# Main.net
KiCad netlist of a schematic drawn in EAGLE
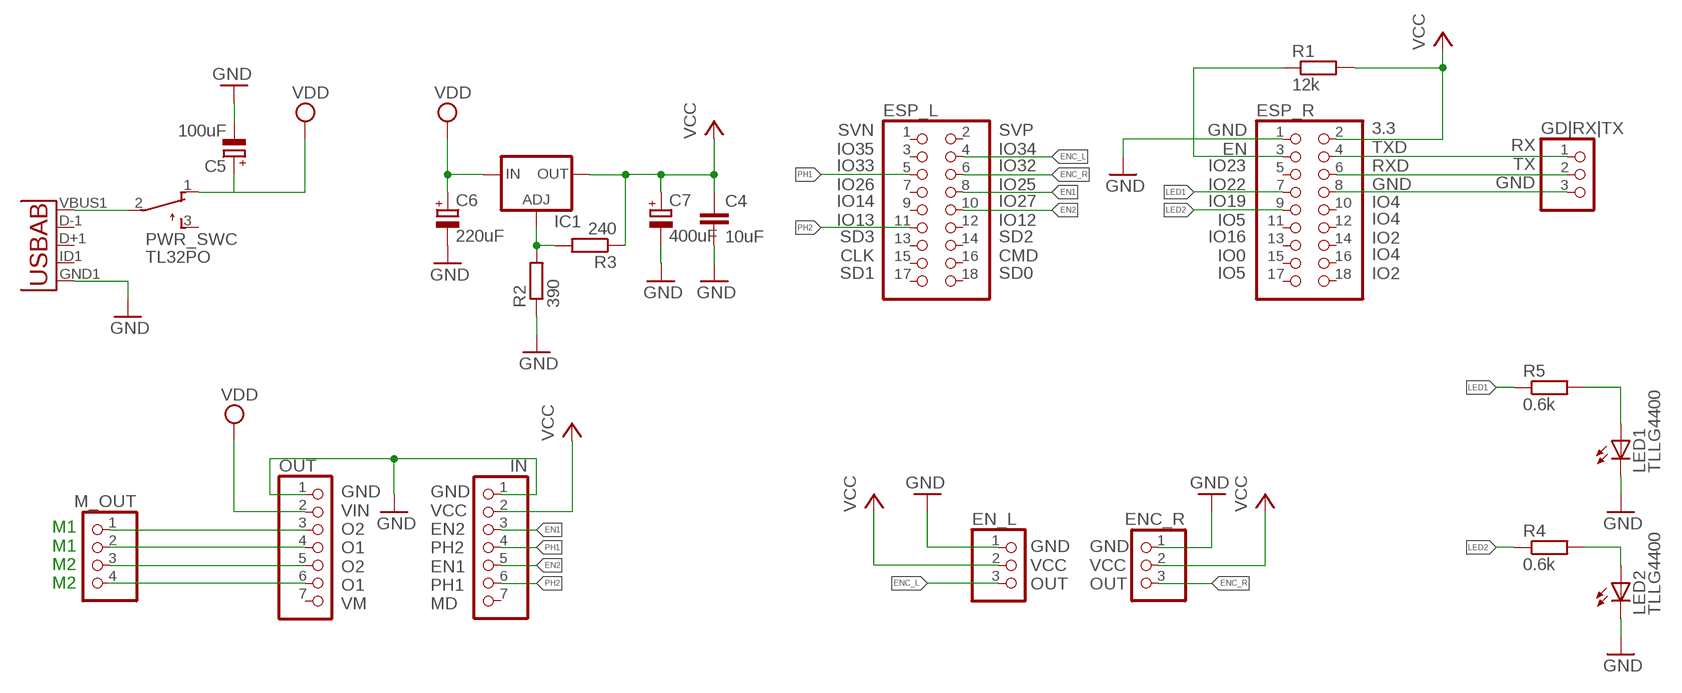
[diagram p0: schematic, sheet 1]

(export (version "E")
  (design (tool "Eeschema 10.0.6"))
  (components
    (comp (ref "C4")
      (value "10uF")
      (footprint "eagle-import:C050-025X075")
      (libsource (lib "eagle-import") (part "C-EU050-025X075"))
    )
    (comp (ref "C5")
      (value "100uF")
      (footprint "eagle-import:E2,5-6")
      (libsource (lib "eagle-import") (part "CPOL-EUE2.5-6"))
    )
    (comp (ref "C6")
      (value "220uF")
      (footprint "eagle-import:E2,5-6")
      (libsource (lib "eagle-import") (part "CPOL-EUE2.5-6"))
    )
    (comp (ref "C7")
      (value "400uF")
      (footprint "eagle-import:E2,5-6")
      (libsource (lib "eagle-import") (part "CPOL-EUE2.5-6"))
    )
    (comp (ref "ENC_R")
      (value "PINHD-1X3")
      (footprint "eagle-import:1X03")
      (libsource (lib "eagle-import") (part "PINHD-1X3"))
    )
    (comp (ref "EN_L")
      (value "PINHD-1X3")
      (footprint "eagle-import:1X03")
      (libsource (lib "eagle-import") (part "PINHD-1X3"))
    )
    (comp (ref "ESP_L")
      (value "PINHD-2X9")
      (footprint "eagle-import:2X09")
      (libsource (lib "eagle-import") (part "PINHD-2X9"))
    )
    (comp (ref "ESP_R")
      (value "PINHD-2X9")
      (footprint "eagle-import:2X09")
      (libsource (lib "eagle-import") (part "PINHD-2X9"))
    )
    (comp (ref "GD|RX|TX")
      (value "PINHD-1X3")
      (footprint "eagle-import:1X03")
      (libsource (lib "eagle-import") (part "PINHD-1X3"))
    )
    (comp (ref "IC1")
      (value "LM317TS")
      (footprint "eagle-import:317TS")
      (libsource (lib "eagle-import") (part "LM317TS"))
    )
    (comp (ref "IN")
      (value "PINHD-1X7")
      (footprint "eagle-import:1X07")
      (libsource (lib "eagle-import") (part "PINHD-1X7"))
    )
    (comp (ref "LED1")
      (value "TLLG4400")
      (footprint "eagle-import:LED3MM")
      (fields (field (name "MF") "VISHAY SEMICONDUCTOR"))
      (libsource (lib "eagle-import") (part "TLLG4400"))
    )
    (comp (ref "LED2")
      (value "TLLG4400")
      (footprint "eagle-import:LED3MM")
      (fields (field (name "MF") "VISHAY SEMICONDUCTOR"))
      (libsource (lib "eagle-import") (part "TLLG4400"))
    )
    (comp (ref "M_OUT")
      (value "PINHD-1X4")
      (footprint "eagle-import:1X04")
      (libsource (lib "eagle-import") (part "PINHD-1X4"))
    )
    (comp (ref "OUT")
      (value "PINHD-1X7")
      (footprint "eagle-import:1X07")
      (libsource (lib "eagle-import") (part "PINHD-1X7"))
    )
    (comp (ref "PWR_SWC")
      (value "TL32PO")
      (footprint "eagle-import:TL3XPO")
      (libsource (lib "eagle-import") (part "TL32PO"))
    )
    (comp (ref "R1")
      (value "12k")
      (footprint "eagle-import:0207_10")
      (libsource (lib "eagle-import") (part "R-EU_0207/10"))
    )
    (comp (ref "R2")
      (value "390")
      (footprint "eagle-import:0207_10")
      (libsource (lib "eagle-import") (part "R-EU_0207/10"))
    )
    (comp (ref "R3")
      (value "240")
      (footprint "eagle-import:0207_10")
      (libsource (lib "eagle-import") (part "R-EU_0207/10"))
    )
    (comp (ref "R4")
      (value "0.6k")
      (footprint "eagle-import:0207_10")
      (libsource (lib "eagle-import") (part "R-EU_0207/10"))
    )
    (comp (ref "R5")
      (value "0.6k")
      (footprint "eagle-import:0207_10")
      (libsource (lib "eagle-import") (part "R-EU_0207/10"))
    )
    (comp (ref "U3")
      (value "USB\"\"")
      (footprint "eagle-import:USB-MICRO-SMD")
      (libsource (lib "eagle-import") (part "USB{dblquote}{dblquote}"))
    )
  )
  (nets
    (net (code "1") (name "EN1") (class "Default")
      (node (ref "ESP_L") (pin "8") (pinfunction "8_8") (pintype "passive"))
      (node (ref "IN") (pin "3") (pinfunction "3_3") (pintype "passive"))
    )
    (net (code "2") (name "EN2") (class "Default")
      (node (ref "ESP_L") (pin "10") (pinfunction "10_10") (pintype "passive"))
      (node (ref "IN") (pin "5") (pinfunction "5_5") (pintype "passive"))
    )
    (net (code "3") (name "ENC_L") (class "Default")
      (node (ref "EN_L") (pin "3") (pinfunction "3_3") (pintype "passive"))
      (node (ref "ESP_L") (pin "4") (pinfunction "4_4") (pintype "passive"))
    )
    (net (code "4") (name "ENC_R") (class "Default")
      (node (ref "ENC_R") (pin "3") (pinfunction "3_3") (pintype "passive"))
      (node (ref "ESP_L") (pin "6") (pinfunction "6_6") (pintype "passive"))
    )
    (net (code "5") (name "GND") (class "Default")
      (node (ref "C4") (pin "2") (pinfunction "2_2") (pintype "passive"))
      (node (ref "C5") (pin "-") (pinfunction "-_-") (pintype "passive"))
      (node (ref "C6") (pin "-") (pinfunction "-_-") (pintype "passive"))
      (node (ref "C7") (pin "-") (pinfunction "-_-") (pintype "passive"))
      (node (ref "ENC_R") (pin "1") (pinfunction "1_1") (pintype "passive"))
      (node (ref "EN_L") (pin "1") (pinfunction "1_1") (pintype "passive"))
      (node (ref "ESP_R") (pin "1") (pinfunction "1_1") (pintype "passive"))
      (node (ref "IN") (pin "1") (pinfunction "1_1") (pintype "passive"))
      (node (ref "LED1") (pin "K") (pinfunction "C_K") (pintype "passive"))
      (node (ref "LED2") (pin "K") (pinfunction "C_K") (pintype "passive"))
      (node (ref "OUT") (pin "1") (pinfunction "1_1") (pintype "passive"))
      (node (ref "R2") (pin "1") (pinfunction "1_1") (pintype "passive"))
      (node (ref "U3") (pin "GND1") (pinfunction "GND_GND1") (pintype "bidirectional"))
    )
    (net (code "6") (name "LED1") (class "Default")
      (node (ref "ESP_R") (pin "7") (pinfunction "7_7") (pintype "passive"))
      (node (ref "R5") (pin "1") (pinfunction "1_1") (pintype "passive"))
    )
    (net (code "7") (name "LED2") (class "Default")
      (node (ref "ESP_R") (pin "9") (pinfunction "9_9") (pintype "passive"))
      (node (ref "R4") (pin "1") (pinfunction "1_1") (pintype "passive"))
    )
    (net (code "8") (name "Net-(ESP_R-Pad3)") (class "Default")
      (node (ref "ESP_R") (pin "3") (pinfunction "3_3") (pintype "passive"))
      (node (ref "R1") (pin "1") (pinfunction "1_1") (pintype "passive"))
    )
    (net (code "9") (name "Net-(ESP_R-Pad4)") (class "Default")
      (node (ref "ESP_R") (pin "4") (pinfunction "4_4") (pintype "passive"))
      (node (ref "GD|RX|TX") (pin "1") (pinfunction "1_1") (pintype "passive"))
    )
    (net (code "10") (name "Net-(ESP_R-Pad6)") (class "Default")
      (node (ref "ESP_R") (pin "6") (pinfunction "6_6") (pintype "passive"))
      (node (ref "GD|RX|TX") (pin "2") (pinfunction "2_2") (pintype "passive"))
    )
    (net (code "11") (name "Net-(ESP_R-Pad8)") (class "Default")
      (node (ref "ESP_R") (pin "8") (pinfunction "8_8") (pintype "passive"))
      (node (ref "GD|RX|TX") (pin "3") (pinfunction "3_3") (pintype "passive"))
    )
    (net (code "12") (name "Net-(IC1-ADJ)") (class "Default")
      (node (ref "IC1") (pin "1") (pinfunction "ADJ_1") (pintype "input"))
      (node (ref "R2") (pin "2") (pinfunction "2_2") (pintype "passive"))
      (node (ref "R3") (pin "2") (pinfunction "2_2") (pintype "passive"))
    )
    (net (code "13") (name "Net-(LED1-PadA)") (class "Default")
      (node (ref "LED1") (pin "A") (pinfunction "A_A") (pintype "passive"))
      (node (ref "R5") (pin "2") (pinfunction "2_2") (pintype "passive"))
    )
    (net (code "14") (name "Net-(LED2-PadA)") (class "Default")
      (node (ref "LED2") (pin "A") (pinfunction "A_A") (pintype "passive"))
      (node (ref "R4") (pin "2") (pinfunction "2_2") (pintype "passive"))
    )
    (net (code "15") (name "Net-(M_OUT-Pad1)") (class "Default")
      (node (ref "M_OUT") (pin "1") (pinfunction "1_1") (pintype "passive"))
      (node (ref "OUT") (pin "3") (pinfunction "3_3") (pintype "passive"))
    )
    (net (code "16") (name "Net-(M_OUT-Pad2)") (class "Default")
      (node (ref "M_OUT") (pin "2") (pinfunction "2_2") (pintype "passive"))
      (node (ref "OUT") (pin "4") (pinfunction "4_4") (pintype "passive"))
    )
    (net (code "17") (name "Net-(M_OUT-Pad3)") (class "Default")
      (node (ref "M_OUT") (pin "3") (pinfunction "3_3") (pintype "passive"))
      (node (ref "OUT") (pin "5") (pinfunction "5_5") (pintype "passive"))
    )
    (net (code "18") (name "Net-(M_OUT-Pad4)") (class "Default")
      (node (ref "M_OUT") (pin "4") (pinfunction "4_4") (pintype "passive"))
      (node (ref "OUT") (pin "6") (pinfunction "6_6") (pintype "passive"))
    )
    (net (code "19") (name "Net-(PWR_SWC-P)") (class "Default")
      (node (ref "PWR_SWC") (pin "2") (pinfunction "P_2") (pintype "passive"))
      (node (ref "U3") (pin "VBUS1") (pinfunction "VBUS_VBUS1") (pintype "bidirectional"))
    )
    (net (code "20") (name "PH1") (class "Default")
      (node (ref "ESP_L") (pin "5") (pinfunction "5_5") (pintype "passive"))
      (node (ref "IN") (pin "4") (pinfunction "4_4") (pintype "passive"))
    )
    (net (code "21") (name "PH2") (class "Default")
      (node (ref "ESP_L") (pin "11") (pinfunction "11_11") (pintype "passive"))
      (node (ref "IN") (pin "6") (pinfunction "6_6") (pintype "passive"))
    )
    (net (code "22") (name "VCC") (class "Default")
      (node (ref "C4") (pin "1") (pinfunction "1_1") (pintype "passive"))
      (node (ref "C7") (pin "+") (pinfunction "+_+") (pintype "passive"))
      (node (ref "ENC_R") (pin "2") (pinfunction "2_2") (pintype "passive"))
      (node (ref "EN_L") (pin "2") (pinfunction "2_2") (pintype "passive"))
      (node (ref "ESP_R") (pin "2") (pinfunction "2_2") (pintype "passive"))
      (node (ref "IC1") (pin "2") (pinfunction "OUT_2") (pintype "passive"))
      (node (ref "IN") (pin "2") (pinfunction "2_2") (pintype "passive"))
      (node (ref "R1") (pin "2") (pinfunction "2_2") (pintype "passive"))
      (node (ref "R3") (pin "1") (pinfunction "1_1") (pintype "passive"))
    )
    (net (code "23") (name "VDD") (class "Default")
      (node (ref "C5") (pin "+") (pinfunction "+_+") (pintype "passive"))
      (node (ref "C6") (pin "+") (pinfunction "+_+") (pintype "passive"))
      (node (ref "IC1") (pin "3") (pinfunction "IN_3") (pintype "input"))
      (node (ref "OUT") (pin "2") (pinfunction "2_2") (pintype "passive"))
      (node (ref "PWR_SWC") (pin "1") (pinfunction "O_1") (pintype "passive"))
    )
    (net (code "24") (name "unconnected-(ESP_L-Pad1)") (class "Default")
      (node (ref "ESP_L") (pin "1") (pinfunction "1_1") (pintype "passive"))
    )
    (net (code "25") (name "unconnected-(ESP_L-Pad2)") (class "Default")
      (node (ref "ESP_L") (pin "2") (pinfunction "2_2") (pintype "passive"))
    )
    (net (code "26") (name "unconnected-(ESP_L-Pad3)") (class "Default")
      (node (ref "ESP_L") (pin "3") (pinfunction "3_3") (pintype "passive"))
    )
    (net (code "27") (name "unconnected-(ESP_L-Pad7)") (class "Default")
      (node (ref "ESP_L") (pin "7") (pinfunction "7_7") (pintype "passive"))
    )
    (net (code "28") (name "unconnected-(ESP_L-Pad9)") (class "Default")
      (node (ref "ESP_L") (pin "9") (pinfunction "9_9") (pintype "passive"))
    )
    (net (code "29") (name "unconnected-(ESP_L-Pad12)") (class "Default")
      (node (ref "ESP_L") (pin "12") (pinfunction "12_12") (pintype "passive"))
    )
    (net (code "30") (name "unconnected-(ESP_L-Pad13)") (class "Default")
      (node (ref "ESP_L") (pin "13") (pinfunction "13_13") (pintype "passive"))
    )
    (net (code "31") (name "unconnected-(ESP_L-Pad14)") (class "Default")
      (node (ref "ESP_L") (pin "14") (pinfunction "14_14") (pintype "passive"))
    )
    (net (code "32") (name "unconnected-(ESP_L-Pad15)") (class "Default")
      (node (ref "ESP_L") (pin "15") (pinfunction "15_15") (pintype "passive"))
    )
    (net (code "33") (name "unconnected-(ESP_L-Pad16)") (class "Default")
      (node (ref "ESP_L") (pin "16") (pinfunction "16_16") (pintype "passive"))
    )
    (net (code "34") (name "unconnected-(ESP_L-Pad17)") (class "Default")
      (node (ref "ESP_L") (pin "17") (pinfunction "17_17") (pintype "passive"))
    )
    (net (code "35") (name "unconnected-(ESP_L-Pad18)") (class "Default")
      (node (ref "ESP_L") (pin "18") (pinfunction "18_18") (pintype "passive"))
    )
    (net (code "36") (name "unconnected-(ESP_R-Pad5)") (class "Default")
      (node (ref "ESP_R") (pin "5") (pinfunction "5_5") (pintype "passive"))
    )
    (net (code "37") (name "unconnected-(ESP_R-Pad10)") (class "Default")
      (node (ref "ESP_R") (pin "10") (pinfunction "10_10") (pintype "passive"))
    )
    (net (code "38") (name "unconnected-(ESP_R-Pad11)") (class "Default")
      (node (ref "ESP_R") (pin "11") (pinfunction "11_11") (pintype "passive"))
    )
    (net (code "39") (name "unconnected-(ESP_R-Pad12)") (class "Default")
      (node (ref "ESP_R") (pin "12") (pinfunction "12_12") (pintype "passive"))
    )
    (net (code "40") (name "unconnected-(ESP_R-Pad13)") (class "Default")
      (node (ref "ESP_R") (pin "13") (pinfunction "13_13") (pintype "passive"))
    )
    (net (code "41") (name "unconnected-(ESP_R-Pad14)") (class "Default")
      (node (ref "ESP_R") (pin "14") (pinfunction "14_14") (pintype "passive"))
    )
    (net (code "42") (name "unconnected-(ESP_R-Pad15)") (class "Default")
      (node (ref "ESP_R") (pin "15") (pinfunction "15_15") (pintype "passive"))
    )
    (net (code "43") (name "unconnected-(ESP_R-Pad16)") (class "Default")
      (node (ref "ESP_R") (pin "16") (pinfunction "16_16") (pintype "passive"))
    )
    (net (code "44") (name "unconnected-(ESP_R-Pad17)") (class "Default")
      (node (ref "ESP_R") (pin "17") (pinfunction "17_17") (pintype "passive"))
    )
    (net (code "45") (name "unconnected-(ESP_R-Pad18)") (class "Default")
      (node (ref "ESP_R") (pin "18") (pinfunction "18_18") (pintype "passive"))
    )
    (net (code "46") (name "unconnected-(IN-Pad7)") (class "Default")
      (node (ref "IN") (pin "7") (pinfunction "7_7") (pintype "passive"))
    )
    (net (code "47") (name "unconnected-(OUT-Pad7)") (class "Default")
      (node (ref "OUT") (pin "7") (pinfunction "7_7") (pintype "passive"))
    )
    (net (code "48") (name "unconnected-(PWR_SWC-S-Pad3)") (class "Default")
      (node (ref "PWR_SWC") (pin "3") (pinfunction "S_3") (pintype "passive"))
    )
    (net (code "49") (name "unconnected-(U3-D+-PadD+1)") (class "Default")
      (node (ref "U3") (pin "D+1") (pinfunction "D+_D+1") (pintype "bidirectional"))
    )
    (net (code "50") (name "unconnected-(U3-D--PadD-1)") (class "Default")
      (node (ref "U3") (pin "D-1") (pinfunction "D-_D-1") (pintype "bidirectional"))
    )
    (net (code "51") (name "unconnected-(U3-USBID-PadID1)") (class "Default")
      (node (ref "U3") (pin "ID1") (pinfunction "USBID_ID1") (pintype "bidirectional"))
    )
  )
)
